# HV_supply.net
KiCad netlist of a schematic drawn in Altium Designer
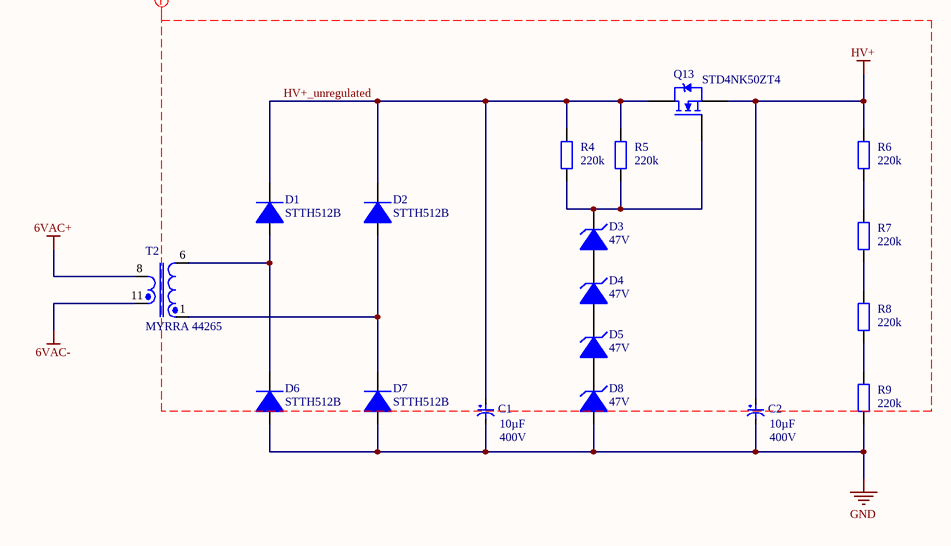
[diagram p0: HV_supply.SchDoc]

(export (version "E")
  (design (tool "Eeschema 10.0.6"))
  (components
    (comp (ref "C1")
      (value "10µF")
      (footprint "EEVEB2G100SM")
      (description "Aluminum Electrolytic Capacitor, 10µF, 400V")
      (fields (field (name "VOLTAGE") "400V") (field (name "Comment") "EEVEB2G100SM"))
      (libsource (lib "Nixie") (part "EEVEB2G100SM"))
    )
    (comp (ref "C2")
      (value "10µF")
      (footprint "EEVEB2G100SM")
      (description "Aluminum Electrolytic Capacitor, 10µF, 400V")
      (fields (field (name "VOLTAGE") "400V") (field (name "Comment") "EEVEB2G100SM"))
      (libsource (lib "Nixie") (part "EEVEB2G100SM"))
    )
    (comp (ref "D1")
      (value "STTH512B")
      (footprint "STTH512B")
      (description "Ultrafast recovery - 1200 V diode")
      (libsource (lib "Nixie") (part "STTH512B"))
    )
    (comp (ref "D2")
      (value "STTH512B")
      (footprint "STTH512B")
      (description "Ultrafast recovery - 1200 V diode")
      (libsource (lib "Nixie") (part "STTH512B"))
    )
    (comp (ref "D3")
      (value "47V")
      (footprint "1SMB5941BT3G")
      (description "47V Zener diode")
      (libsource (lib "Nixie") (part "1SMB5941BT3G"))
    )
    (comp (ref "D4")
      (value "47V")
      (footprint "1SMB5941BT3G")
      (description "47V Zener diode")
      (libsource (lib "Nixie") (part "1SMB5941BT3G"))
    )
    (comp (ref "D5")
      (value "47V")
      (footprint "1SMB5941BT3G")
      (description "47V Zener diode")
      (libsource (lib "Nixie") (part "1SMB5941BT3G"))
    )
    (comp (ref "D6")
      (value "STTH512B")
      (footprint "STTH512B")
      (description "Ultrafast recovery - 1200 V diode")
      (libsource (lib "Nixie") (part "STTH512B"))
    )
    (comp (ref "D7")
      (value "STTH512B")
      (footprint "STTH512B")
      (description "Ultrafast recovery - 1200 V diode")
      (libsource (lib "Nixie") (part "STTH512B"))
    )
    (comp (ref "D8")
      (value "47V")
      (footprint "1SMB5941BT3G")
      (description "47V Zener diode")
      (libsource (lib "Nixie") (part "1SMB5941BT3G"))
    )
    (comp (ref "Q13")
      (value "STD4NK50ZT4")
      (footprint "STD4NK50ZT4")
      (description "N-CHANNEL 500V - 2.4Ω - 3A DPAK MOSFET")
      (libsource (lib "Nixie") (part "STD4NK50ZT4"))
    )
    (comp (ref "R4")
      (value "220k")
      (footprint "RES0805")
      (description "Chip resistor 220k 0805")
      (libsource (lib "Nixie") (part "220k 0805"))
    )
    (comp (ref "R5")
      (value "220k")
      (footprint "RES0805")
      (description "Chip resistor 220k 0805")
      (libsource (lib "Nixie") (part "220k 0805"))
    )
    (comp (ref "R6")
      (value "220k")
      (footprint "RES0805")
      (description "Chip resistor 220k 0805")
      (libsource (lib "Nixie") (part "220k 0805"))
    )
    (comp (ref "R7")
      (value "220k")
      (footprint "RES0805")
      (description "Chip resistor 220k 0805")
      (libsource (lib "Nixie") (part "220k 0805"))
    )
    (comp (ref "R8")
      (value "220k")
      (footprint "RES0805")
      (description "Chip resistor 220k 0805")
      (libsource (lib "Nixie") (part "220k 0805"))
    )
    (comp (ref "R9")
      (value "220k")
      (footprint "RES0805")
      (description "Chip resistor 220k 0805")
      (libsource (lib "Nixie") (part "220k 0805"))
    )
    (comp (ref "T2")
      (value "MYRRA 44265")
      (footprint "MYRRA_44265")
      (description "Isolation Transformer 10 VA, 230V, 6V")
      (libsource (lib "Nixie") (part "MYRRA 44265"))
    )
  )
  (nets
    (net (code "1") (name "/HV+_unregulated") (class "Default")
      (node (ref "C1") (pin "1") (pinfunction "1_1") (pintype "passive"))
      (node (ref "D1") (pin "K") (pinfunction "K_K") (pintype "passive"))
      (node (ref "D2") (pin "K") (pinfunction "K_K") (pintype "passive"))
      (node (ref "Q13") (pin "D") (pinfunction "D_D") (pintype "passive"))
      (node (ref "R4") (pin "2") (pinfunction "2_2") (pintype "passive"))
      (node (ref "R5") (pin "2") (pinfunction "2_2") (pintype "passive"))
    )
    (net (code "2") (name "6VAC+") (class "Default")
      (node (ref "T2") (pin "8") (pinfunction "8_8") (pintype "passive"))
    )
    (net (code "3") (name "6VAC-") (class "Default")
      (node (ref "T2") (pin "11") (pinfunction "11_11") (pintype "passive"))
    )
    (net (code "4") (name "GND") (class "Default")
      (node (ref "C1") (pin "2") (pinfunction "2_2") (pintype "passive"))
      (node (ref "C2") (pin "2") (pinfunction "2_2") (pintype "passive"))
      (node (ref "D6") (pin "A") (pinfunction "A_A") (pintype "passive"))
      (node (ref "D7") (pin "A") (pinfunction "A_A") (pintype "passive"))
      (node (ref "D8") (pin "A") (pinfunction "A_A") (pintype "passive"))
      (node (ref "R9") (pin "1") (pinfunction "1_1") (pintype "passive"))
    )
    (net (code "5") (name "HV+") (class "Default")
      (node (ref "C2") (pin "1") (pinfunction "1_1") (pintype "passive"))
      (node (ref "Q13") (pin "s") (pinfunction "S_s") (pintype "passive"))
      (node (ref "R6") (pin "2") (pinfunction "2_2") (pintype "passive"))
    )
    (net (code "6") (name "Net-(D1-PadA)") (class "Default")
      (node (ref "D1") (pin "A") (pinfunction "A_A") (pintype "passive"))
      (node (ref "D6") (pin "K") (pinfunction "K_K") (pintype "passive"))
      (node (ref "T2") (pin "6") (pinfunction "6_6") (pintype "passive"))
    )
    (net (code "7") (name "Net-(D2-PadA)") (class "Default")
      (node (ref "D2") (pin "A") (pinfunction "A_A") (pintype "passive"))
      (node (ref "D7") (pin "K") (pinfunction "K_K") (pintype "passive"))
      (node (ref "T2") (pin "1") (pinfunction "1_1") (pintype "passive"))
    )
    (net (code "8") (name "Net-(D3-PadA)") (class "Default")
      (node (ref "D3") (pin "A") (pinfunction "A_A") (pintype "passive"))
      (node (ref "D4") (pin "K") (pinfunction "K_K") (pintype "passive"))
    )
    (net (code "9") (name "Net-(D3-PadK)") (class "Default")
      (node (ref "D3") (pin "K") (pinfunction "K_K") (pintype "passive"))
      (node (ref "Q13") (pin "G") (pinfunction "G_G") (pintype "passive"))
      (node (ref "R4") (pin "1") (pinfunction "1_1") (pintype "passive"))
      (node (ref "R5") (pin "1") (pinfunction "1_1") (pintype "passive"))
    )
    (net (code "10") (name "Net-(D4-PadA)") (class "Default")
      (node (ref "D4") (pin "A") (pinfunction "A_A") (pintype "passive"))
      (node (ref "D5") (pin "K") (pinfunction "K_K") (pintype "passive"))
    )
    (net (code "11") (name "Net-(D5-PadA)") (class "Default")
      (node (ref "D5") (pin "A") (pinfunction "A_A") (pintype "passive"))
      (node (ref "D8") (pin "K") (pinfunction "K_K") (pintype "passive"))
    )
    (net (code "12") (name "Net-(R6-Pad1)") (class "Default")
      (node (ref "R6") (pin "1") (pinfunction "1_1") (pintype "passive"))
      (node (ref "R7") (pin "2") (pinfunction "2_2") (pintype "passive"))
    )
    (net (code "13") (name "Net-(R7-Pad1)") (class "Default")
      (node (ref "R7") (pin "1") (pinfunction "1_1") (pintype "passive"))
      (node (ref "R8") (pin "2") (pinfunction "2_2") (pintype "passive"))
    )
    (net (code "14") (name "Net-(R8-Pad1)") (class "Default")
      (node (ref "R8") (pin "1") (pinfunction "1_1") (pintype "passive"))
      (node (ref "R9") (pin "2") (pinfunction "2_2") (pintype "passive"))
    )
  )
)
